# LDO.net
KiCad netlist of a schematic drawn in Altium Designer
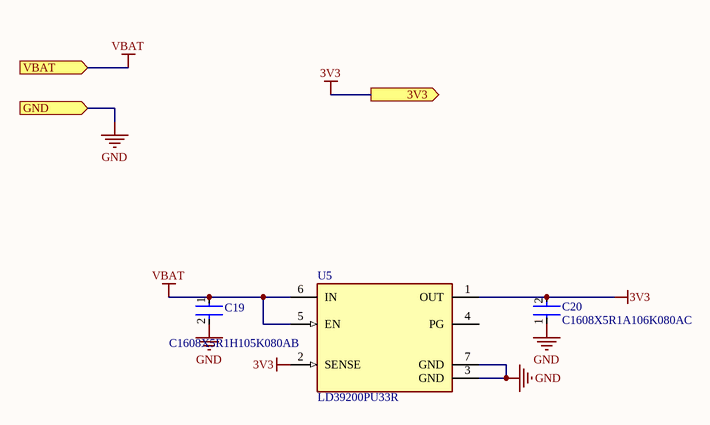
[diagram p0: LDO.SchDoc]

(export (version "E")
  (design (tool "Eeschema 10.0.6"))
  (components
    (comp (ref "C19")
      (value "C1608X5R1H105K080AB")
      (footprint "FP-C1608-080-0_1-IPC_B")
      (description "Multilayer Ceramic Capacitors 1μF ±10% 50V X5R SMD 0603")
      (fields (field (name "VOLTAGE") "50V") (field (name "TOLERANCE") "10%"))
      (libsource (lib "Altium Content Vault") (part "236180d848d6139a670b325ea6854c9"))
    )
    (comp (ref "C20")
      (value "C1608X5R1A106K080AC")
      (footprint "FP-C1608-080-0_1-MFG")
      (description "Multilayer Ceramic Capacitors 10μF ±10% 10V X5R SMD 0603")
      (fields (field (name "VOLTAGE") "10V") (field (name "TOLERANCE") "10%"))
      (libsource (lib "Altium Content Vault") (part "236180d848d6139a670b325ea6854c9"))
    )
    (comp (ref "U5")
      (value "LD39200PU33R")
      (footprint "FP-DFN6-7946637-MFG")
      (description "IC REG LINEAR 3.3V 2A 6DFN")
      (libsource (lib "Altium Content Vault") (part "f0cfe00d12cb984572f50007c934a2d"))
    )
  )
  (nets
    (net (code "1") (name "3V3") (class "Default")
      (node (ref "C20") (pin "2") (pinfunction "2_2") (pintype "passive"))
      (node (ref "U5") (pin "1") (pinfunction "OUT_1") (pintype "power_in"))
      (node (ref "U5") (pin "2") (pinfunction "SENSE_2") (pintype "input"))
    )
    (net (code "2") (name "GND") (class "Default")
      (node (ref "C19") (pin "2") (pinfunction "2_2") (pintype "passive"))
      (node (ref "C20") (pin "1") (pinfunction "1_1") (pintype "passive"))
      (node (ref "U5") (pin "3") (pinfunction "GND_3") (pintype "power_in"))
      (node (ref "U5") (pin "7") (pinfunction "GND_7") (pintype "power_in"))
    )
    (net (code "3") (name "VBAT") (class "Default")
      (node (ref "C19") (pin "1") (pinfunction "1_1") (pintype "passive"))
      (node (ref "U5") (pin "5") (pinfunction "EN_5") (pintype "input"))
      (node (ref "U5") (pin "6") (pinfunction "IN_6") (pintype "power_in"))
    )
    (net (code "4") (name "unconnected-(U5-PG-Pad4)") (class "Default")
      (node (ref "U5") (pin "4") (pinfunction "PG_4") (pintype "open_collector"))
    )
  )
)
